# DAC.net
KiCad netlist of a schematic drawn in Altium Designer
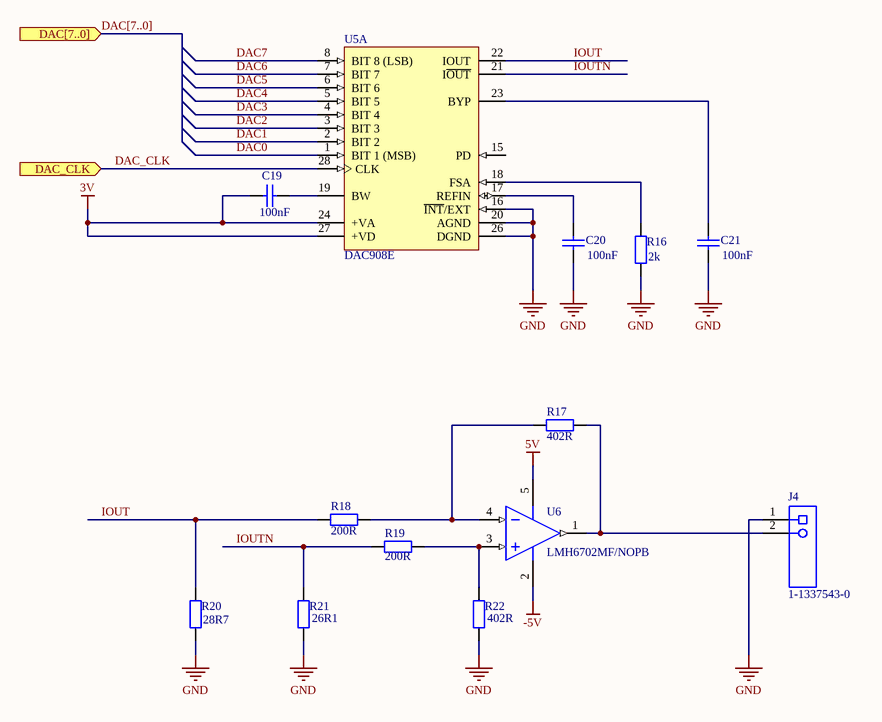
[diagram p0: DAC.SchDoc]

(export (version "E")
  (design (tool "Eeschema 10.0.6"))
  (components
    (comp (ref "C19")
      (value "100nF")
      (footprint "RAD-0.3")
      (description "Capacitor")
      (fields (field (name "Comment") "Cap") (field (name "PUBLISHER") "Altium Limited"))
      (libsource (lib "Miscellaneous Devices") (part "Cap"))
    )
    (comp (ref "C20")
      (value "100nF")
      (footprint "RAD-0.3")
      (description "Capacitor")
      (fields (field (name "Comment") "Cap") (field (name "PUBLISHER") "Altium Limited"))
      (libsource (lib "Miscellaneous Devices") (part "Cap"))
    )
    (comp (ref "C21")
      (value "100nF")
      (footprint "RAD-0.3")
      (description "Capacitor")
      (fields (field (name "Comment") "Cap") (field (name "PUBLISHER") "Altium Limited"))
      (libsource (lib "Miscellaneous Devices") (part "Cap"))
    )
    (comp (ref "J4")
      (value "1-1337543-0")
      (footprint "TECO-1-1337543-0_V")
      (fields (field (name "MANUFACTURER") "TE Connectivity"))
      (libsource (lib "Altium Content Vault") (part "CN-1P-F-R2_A"))
    )
    (comp (ref "R16")
      (value "2k")
      (footprint "AXIAL-0.4")
      (description "Resistor")
      (fields (field (name "Comment") "Res2") (field (name "PUBLISHER") "Altium Limited"))
      (libsource (lib "") (part "Res2_1"))
    )
    (comp (ref "R17")
      (value "402R")
      (footprint "AXIAL-0.4")
      (description "Resistor")
      (fields (field (name "Comment") "Res2") (field (name "PUBLISHER") "Altium Limited"))
      (libsource (lib "Miscellaneous Devices") (part "Res2"))
    )
    (comp (ref "R18")
      (value "200R")
      (footprint "AXIAL-0.4")
      (description "Resistor")
      (fields (field (name "Comment") "Res2") (field (name "PUBLISHER") "Altium Limited"))
      (libsource (lib "") (part "Res2_2"))
    )
    (comp (ref "R19")
      (value "200R")
      (footprint "AXIAL-0.4")
      (description "Resistor")
      (fields (field (name "Comment") "Res2") (field (name "PUBLISHER") "Altium Limited"))
      (libsource (lib "") (part "Res2_2"))
    )
    (comp (ref "R20")
      (value "28R7")
      (footprint "AXIAL-0.4")
      (description "Resistor")
      (fields (field (name "Comment") "Res2") (field (name "PUBLISHER") "Altium Limited"))
      (libsource (lib "") (part "Res2_1"))
    )
    (comp (ref "R21")
      (value "26R1")
      (footprint "AXIAL-0.4")
      (description "Resistor")
      (fields (field (name "Comment") "Res2") (field (name "PUBLISHER") "Altium Limited"))
      (libsource (lib "") (part "Res2_1"))
    )
    (comp (ref "R22")
      (value "402R")
      (footprint "AXIAL-0.4")
      (description "Resistor")
      (fields (field (name "Comment") "Res2") (field (name "PUBLISHER") "Altium Limited"))
      (libsource (lib "") (part "Res2_1"))
    )
    (comp (ref "U5")
      (value "DAC908E")
      (footprint "TI-PW28_N")
      (fields (field (name "MANUFACTURER") "Texas Instruments"))
      (libsource (lib "Altium Content Vault") (part "TI-DAC908PW28"))
    )
    (comp (ref "U6")
      (value "LMH6702MF/NOPB")
      (footprint "DBV0005A_N")
      (description "1.7 GHz, Ultra Low Distortion, Wideband Op Amp, 5-pin SOT-23, Pb-Free")
      (fields (field (name "MANUFACTURER") "Texas Instruments"))
      (libsource (lib "Altium Content Vault") (part "AMP-OPA-LM7121-5"))
    )
  )
  (nets
    (net (code "1") (name "-5V") (class "Default")
      (node (ref "U6") (pin "2") (pinfunction "V-_2") (pintype "power_in"))
    )
    (net (code "2") (name "/DAC0") (class "Default")
      (node (ref "U5") (pin "1") (pinfunction "BIT_1_(MSB)_1") (pintype "input"))
    )
    (net (code "3") (name "/DAC1") (class "Default")
      (node (ref "U5") (pin "2") (pinfunction "BIT_2_2") (pintype "input"))
    )
    (net (code "4") (name "/DAC2") (class "Default")
      (node (ref "U5") (pin "3") (pinfunction "BIT_3_3") (pintype "input"))
    )
    (net (code "5") (name "/DAC3") (class "Default")
      (node (ref "U5") (pin "4") (pinfunction "BIT_4_4") (pintype "input"))
    )
    (net (code "6") (name "/DAC4") (class "Default")
      (node (ref "U5") (pin "5") (pinfunction "BIT_5_5") (pintype "input"))
    )
    (net (code "7") (name "/DAC5") (class "Default")
      (node (ref "U5") (pin "6") (pinfunction "BIT_6_6") (pintype "input"))
    )
    (net (code "8") (name "/DAC6") (class "Default")
      (node (ref "U5") (pin "7") (pinfunction "BIT_7_7") (pintype "input"))
    )
    (net (code "9") (name "/DAC7") (class "Default")
      (node (ref "U5") (pin "8") (pinfunction "BIT_8_(LSB)_8") (pintype "input"))
    )
    (net (code "11") (name "/DAC_CLK") (class "Default")
      (node (ref "U5") (pin "28") (pinfunction "CLK_28") (pintype "input"))
    )
    (net (code "12") (name "/IOUT") (class "Default")
      (node (ref "R18") (pin "1") (pinfunction "1_1") (pintype "passive"))
      (node (ref "R20") (pin "2") (pinfunction "2_2") (pintype "passive"))
      (node (ref "U5") (pin "22") (pinfunction "IOUT_22") (pintype "tri_state"))
    )
    (net (code "13") (name "/IOUTN") (class "Default")
      (node (ref "R19") (pin "1") (pinfunction "1_1") (pintype "passive"))
      (node (ref "R21") (pin "2") (pinfunction "2_2") (pintype "passive"))
      (node (ref "U5") (pin "21") (pinfunction "I~{OUT}_21") (pintype "tri_state"))
    )
    (net (code "14") (name "3V") (class "Default")
      (node (ref "C19") (pin "1") (pinfunction "1_1") (pintype "passive"))
      (node (ref "U5") (pin "24") (pinfunction "+VA_24") (pintype "power_in"))
      (node (ref "U5") (pin "27") (pinfunction "+VD_27") (pintype "power_in"))
    )
    (net (code "15") (name "5V") (class "Default")
      (node (ref "U6") (pin "5") (pinfunction "V+_5") (pintype "power_in"))
    )
    (net (code "16") (name "GND") (class "Default")
      (node (ref "C20") (pin "1") (pinfunction "1_1") (pintype "passive"))
      (node (ref "C21") (pin "1") (pinfunction "1_1") (pintype "passive"))
      (node (ref "J4") (pin "1") (pinfunction "1_1") (pintype "passive"))
      (node (ref "R16") (pin "1") (pinfunction "1_1") (pintype "passive"))
      (node (ref "R20") (pin "1") (pinfunction "1_1") (pintype "passive"))
      (node (ref "R21") (pin "1") (pinfunction "1_1") (pintype "passive"))
      (node (ref "R22") (pin "1") (pinfunction "1_1") (pintype "passive"))
      (node (ref "U5") (pin "16") (pinfunction "~{INT}/EXT_16") (pintype "input"))
      (node (ref "U5") (pin "20") (pinfunction "AGND_20") (pintype "power_in"))
      (node (ref "U5") (pin "26") (pinfunction "DGND_26") (pintype "power_in"))
    )
    (net (code "17") (name "Net-(U5A-BW)") (class "Default")
      (node (ref "C19") (pin "2") (pinfunction "2_2") (pintype "passive"))
      (node (ref "U5") (pin "19") (pinfunction "BW_19") (pintype "passive"))
    )
    (net (code "18") (name "Net-(U5A-BYP)") (class "Default")
      (node (ref "C21") (pin "2") (pinfunction "2_2") (pintype "passive"))
      (node (ref "U5") (pin "23") (pinfunction "BYP_23") (pintype "passive"))
    )
    (net (code "19") (name "Net-(U5A-FSA)") (class "Default")
      (node (ref "R16") (pin "2") (pinfunction "2_2") (pintype "passive"))
      (node (ref "U5") (pin "18") (pinfunction "FSA_18") (pintype "input"))
    )
    (net (code "20") (name "Net-(U5A-REFIN)") (class "Default")
      (node (ref "C20") (pin "2") (pinfunction "2_2") (pintype "passive"))
      (node (ref "U5") (pin "17") (pinfunction "REFIN_17") (pintype "bidirectional"))
    )
    (net (code "21") (name "Net-(U6-IN+)") (class "Default")
      (node (ref "R19") (pin "2") (pinfunction "2_2") (pintype "passive"))
      (node (ref "R22") (pin "2") (pinfunction "2_2") (pintype "passive"))
      (node (ref "U6") (pin "3") (pinfunction "IN+_3") (pintype "input"))
    )
    (net (code "22") (name "Net-(U6-IN-)") (class "Default")
      (node (ref "R17") (pin "2") (pinfunction "2_2") (pintype "passive"))
      (node (ref "R18") (pin "2") (pinfunction "2_2") (pintype "passive"))
      (node (ref "U6") (pin "4") (pinfunction "IN-_4") (pintype "input"))
    )
    (net (code "23") (name "Net-(U6-OUT)") (class "Default")
      (node (ref "J4") (pin "2") (pinfunction "2_2") (pintype "passive"))
      (node (ref "R17") (pin "1") (pinfunction "1_1") (pintype "passive"))
      (node (ref "U6") (pin "1") (pinfunction "OUT_1") (pintype "output"))
    )
    (net (code "24") (name "unconnected-(U5A-PD-Pad15)") (class "Default")
      (node (ref "U5") (pin "15") (pinfunction "PD_15") (pintype "input"))
    )
  )
)
